# motherboard.net
KiCad netlist of a schematic drawn in Altium Designer
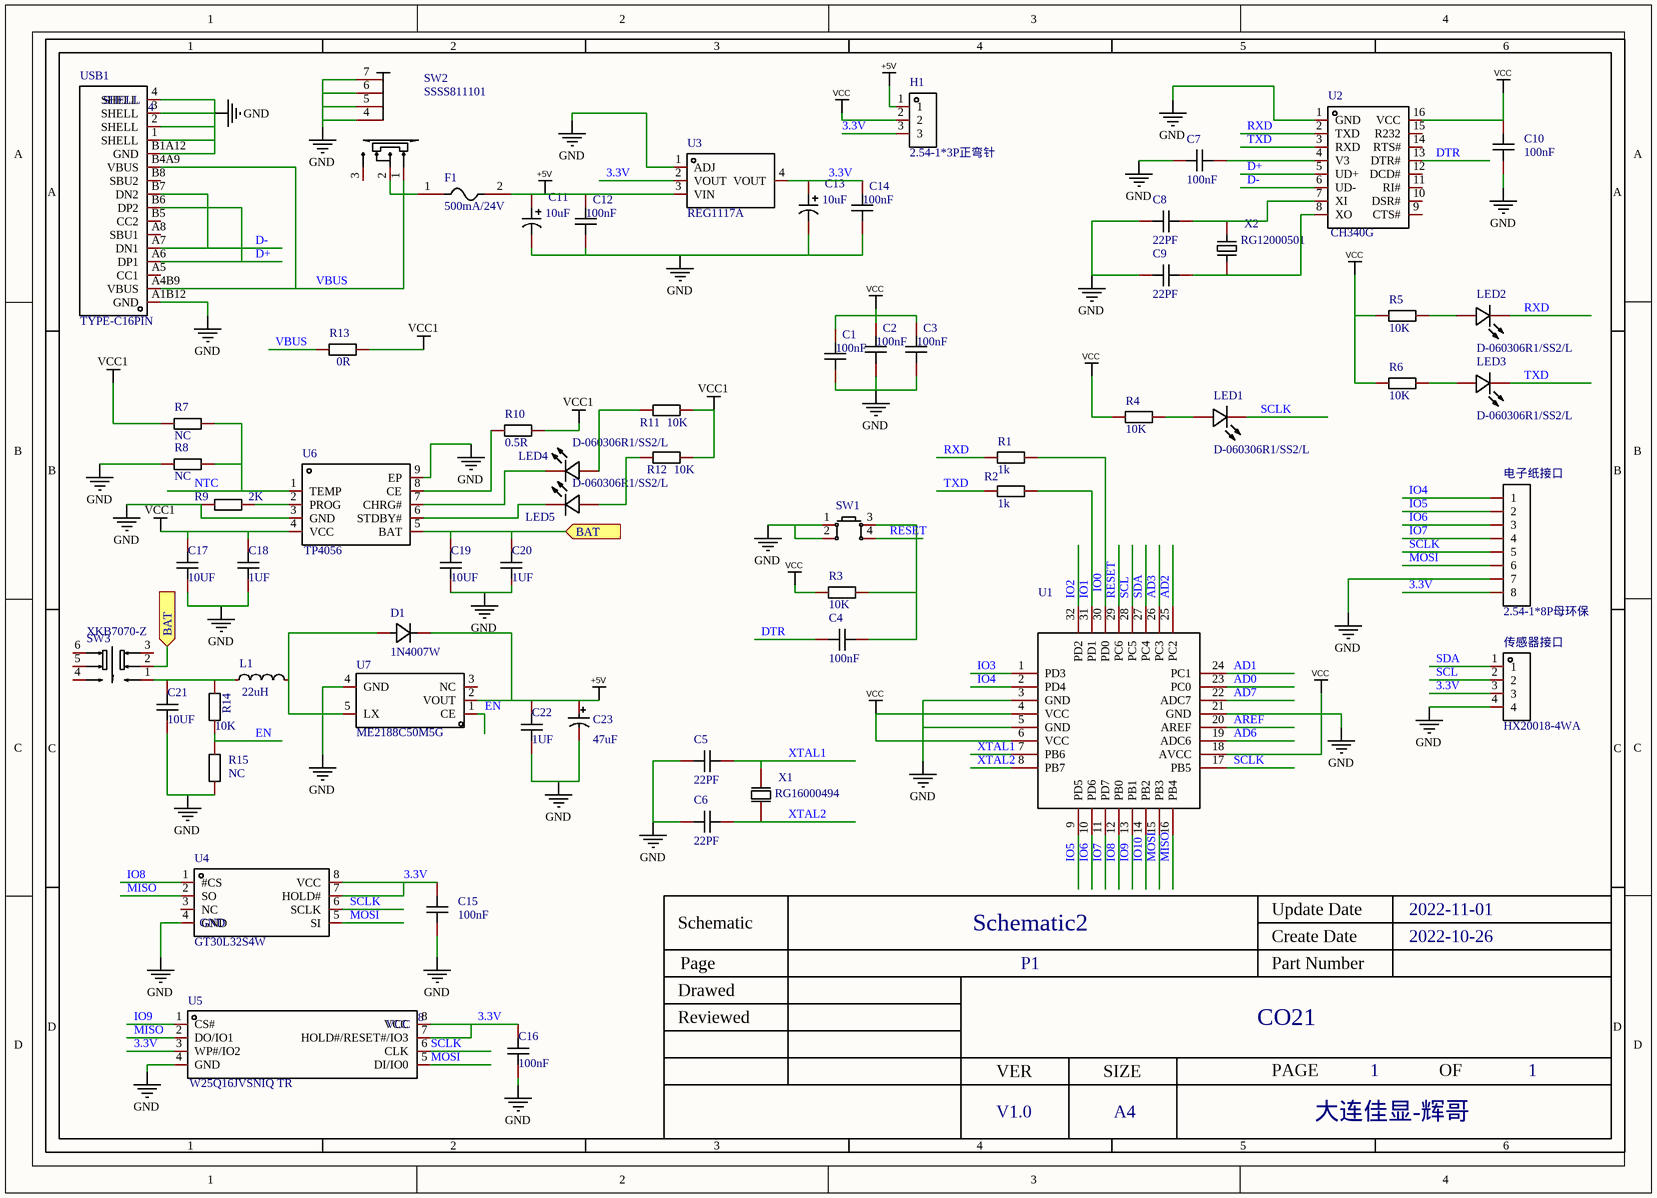
[diagram p0: motherboard.schdoc]

(export (version "E")
  (design (tool "Eeschema 10.0.6"))
  (components
    (comp (ref "C1")
      (value "100nF")
      (fields (field (name "NAME") "100nF"))
      (libsource (lib "altium-import") (part "root_1_CAP_0603_"))
    )
    (comp (ref "C2")
      (value "100nF")
      (fields (field (name "NAME") "100nF"))
      (libsource (lib "altium-import") (part "root_1_CAP_0603_"))
    )
    (comp (ref "C3")
      (value "100nF")
      (fields (field (name "NAME") "100nF"))
      (libsource (lib "altium-import") (part "root_1_CAP_0603_"))
    )
    (comp (ref "C4")
      (value "100nF")
      (fields (field (name "NAME") "100nF"))
      (libsource (lib "altium-import") (part "root_2_CAP_0603_"))
    )
    (comp (ref "C5")
      (value "22PF")
      (fields (field (name "NAME") "22PF"))
      (libsource (lib "altium-import") (part "root_2_CAP_0603_"))
    )
    (comp (ref "C6")
      (value "22PF")
      (fields (field (name "NAME") "22PF"))
      (libsource (lib "altium-import") (part "root_2_CAP_0603_"))
    )
    (comp (ref "C7")
      (value "100nF")
      (fields (field (name "NAME") "100nF"))
      (libsource (lib "altium-import") (part "root_0_CAP_0603_"))
    )
    (comp (ref "C8")
      (value "22PF")
      (fields (field (name "NAME") "22PF"))
      (libsource (lib "altium-import") (part "root_2_CAP_0603_"))
    )
    (comp (ref "C9")
      (value "22PF")
      (fields (field (name "NAME") "22PF"))
      (libsource (lib "altium-import") (part "root_2_CAP_0603_"))
    )
    (comp (ref "C10")
      (value "100nF")
      (fields (field (name "NAME") "100nF"))
      (libsource (lib "altium-import") (part "root_1_CAP_0603_"))
    )
    (comp (ref "C11")
      (value "10uF")
      (description "容值:10uF;精度:±10%;额定电压:20V;工作温度:-55~+125;")
      (fields
        (field (name "NAME") "10uF")
        (field (name "MANUFACTURER") "CEC(振华新云)")
        (field (name "MANUFACTURER PART") "CA45A-B-20V-10UF-K")
      )
      (libsource (lib "altium-import") (part "root_3_CA45A-B-20V-10UF-K_"))
    )
    (comp (ref "C12")
      (value "100nF")
      (fields (field (name "NAME") "100nF"))
      (libsource (lib "altium-import") (part "root_1_CAP_0603_"))
    )
    (comp (ref "C13")
      (value "10uF")
      (description "容值:10uF;精度:±10%;额定电压:20V;工作温度:-55~+125;")
      (fields
        (field (name "NAME") "10uF")
        (field (name "MANUFACTURER") "CEC(振华新云)")
        (field (name "MANUFACTURER PART") "CA45A-B-20V-10UF-K")
      )
      (libsource (lib "altium-import") (part "root_3_CA45A-B-20V-10UF-K_"))
    )
    (comp (ref "C14")
      (value "100nF")
      (fields (field (name "NAME") "100nF"))
      (libsource (lib "altium-import") (part "root_1_CAP_0603_"))
    )
    (comp (ref "C15")
      (value "100nF")
      (fields (field (name "NAME") "100nF"))
      (libsource (lib "altium-import") (part "root_3_CAP_0603_"))
    )
    (comp (ref "C16")
      (value "100nF")
      (fields (field (name "NAME") "100nF"))
      (libsource (lib "altium-import") (part "root_3_CAP_0603_"))
    )
    (comp (ref "C17")
      (value "10UF")
      (fields (field (name "NAME") "10UF"))
      (libsource (lib "altium-import") (part "root_3_CAP_0603_"))
    )
    (comp (ref "C18")
      (value "1UF")
      (fields (field (name "NAME") "1UF"))
      (libsource (lib "altium-import") (part "root_3_CAP_0603_"))
    )
    (comp (ref "C19")
      (value "10UF")
      (fields (field (name "NAME") "10UF"))
      (libsource (lib "altium-import") (part "root_3_CAP_0603_"))
    )
    (comp (ref "C20")
      (value "1UF")
      (fields (field (name "NAME") "1UF"))
      (libsource (lib "altium-import") (part "root_3_CAP_0603_"))
    )
    (comp (ref "C21")
      (value "10UF")
      (fields (field (name "NAME") "10UF"))
      (libsource (lib "altium-import") (part "root_3_CAP_0603_"))
    )
    (comp (ref "C22")
      (value "1UF")
      (fields (field (name "NAME") "1UF"))
      (libsource (lib "altium-import") (part "root_3_CAP_0603_"))
    )
    (comp (ref "C23")
      (value "47uF")
      (description "容值:47uF;精度:±20%;额定电压:10V;电容体直径:4mm;电容体长度:5mm;脚间距:1.5mm;工作寿命:1000hrs@105;")
      (fields
        (field (name "NAME") "47uF")
        (field (name "MANUFACTURER") "CX(承兴)")
        (field (name "MANUFACTURER PART") "KF476M010C05RR0VH2FP0")
      )
      (libsource (lib "altium-import") (part "root_3_KF476M010C05RR0VH2FP0_"))
    )
    (comp (ref "D1")
      (value "1N4007W")
      (description "二极管配置:独立式;直流反向耐压(Vr):1kV;平均整流电流(Io):1A;正向压降(Vf):1.1V@1A;反向电流(Ir):5A@1kV;")
      (fields (field (name "NAME") "1N4007W") (field (name "MANUFACTURER") "ST(先科)"))
      (libsource (lib "altium-import") (part "root_2_1N4007W_C725740_"))
    )
    (comp (ref "F1")
      (value "500mA/24V")
      (fields (field (name "NAME") "500mA/24V") (field (name "MANUFACTURER") "DOWO(东沃)"))
      (libsource (lib "altium-import") (part "root_0_500mA/24V_"))
    )
    (comp (ref "H1")
      (value "2.54-1*3P正弯针")
      (fields (field (name "NAME") "2.54-1*3P正弯针") (field (name "MANUFACTURER") "BOOMELE(博穆精密)"))
      (libsource (lib "altium-import") (part "root_0_2.54-1*3P正弯针_"))
    )
    (comp (ref "L1")
      (value "22uH")
      (description "电感值:22uH;精度:±20%;额定电流:1.4A;直流电阻(DCR):174mΩ;")
      (fields
        (field (name "NAME") "22uH")
        (field (name "MANUFACTURER") "SXN(顺翔诺)")
        (field (name "MANUFACTURER PART") "SMNR5040-220MT")
      )
      (libsource (lib "altium-import") (part "root_0_SMNR5040-220MT_"))
    )
    (comp (ref "LED1")
      (value "D-060306R1/SS2/L")
      (description "发光颜色:红灯;")
      (fields (field (name "NAME") "D-060306R1/SS2/L") (field (name "MANUFACTURER") "方舟 ARKLED"))
      (libsource (lib "altium-import") (part "root_2_D-060306R1/SS2/L_"))
    )
    (comp (ref "LED2")
      (value "D-060306R1/SS2/L")
      (description "发光颜色:红灯;")
      (fields (field (name "NAME") "D-060306R1/SS2/L") (field (name "MANUFACTURER") "方舟 ARKLED"))
      (libsource (lib "altium-import") (part "root_2_D-060306R1/SS2/L_"))
    )
    (comp (ref "LED3")
      (value "D-060306R1/SS2/L")
      (description "发光颜色:红灯;")
      (fields (field (name "NAME") "D-060306R1/SS2/L") (field (name "MANUFACTURER") "方舟 ARKLED"))
      (libsource (lib "altium-import") (part "root_2_D-060306R1/SS2/L_"))
    )
    (comp (ref "LED4")
      (value "D-060306R1/SS2/L")
      (description "发光颜色:红灯;")
      (fields (field (name "NAME") "D-060306R1/SS2/L") (field (name "MANUFACTURER") "方舟 ARKLED"))
      (libsource (lib "altium-import") (part "root_0_D-060306R1/SS2/L_"))
    )
    (comp (ref "LED5")
      (value "D-060306R1/SS2/L")
      (description "发光颜色:红灯;")
      (fields (field (name "NAME") "D-060306R1/SS2/L") (field (name "MANUFACTURER") "方舟 ARKLED"))
      (libsource (lib "altium-import") (part "root_0_D-060306R1/SS2/L_"))
    )
    (comp (ref "R1")
      (value "1k")
      (fields (field (name "NAME") "1k"))
      (libsource (lib "altium-import") (part "root_0_Res_0603_"))
    )
    (comp (ref "R2")
      (value "1k")
      (fields (field (name "NAME") "1k"))
      (libsource (lib "altium-import") (part "root_0_Res_0603_"))
    )
    (comp (ref "R3")
      (value "10K")
      (fields (field (name "NAME") "10K"))
      (libsource (lib "altium-import") (part "root_0_Res_0603_"))
    )
    (comp (ref "R4")
      (value "10K")
      (fields (field (name "NAME") "10K"))
      (libsource (lib "altium-import") (part "root_0_Res_0603_"))
    )
    (comp (ref "R5")
      (value "10K")
      (fields (field (name "NAME") "10K"))
      (libsource (lib "altium-import") (part "root_0_Res_0603_"))
    )
    (comp (ref "R6")
      (value "10K")
      (fields (field (name "NAME") "10K"))
      (libsource (lib "altium-import") (part "root_0_Res_0603_"))
    )
    (comp (ref "R7")
      (value "NC")
      (fields (field (name "NAME") "NC"))
      (libsource (lib "altium-import") (part "root_0_Res_0603_"))
    )
    (comp (ref "R8")
      (value "NC")
      (fields (field (name "NAME") "NC"))
      (libsource (lib "altium-import") (part "root_0_Res_0603_"))
    )
    (comp (ref "R9")
      (value "2K")
      (fields (field (name "NAME") "2K"))
      (libsource (lib "altium-import") (part "root_0_Res_0603_"))
    )
    (comp (ref "R10")
      (value "0.5R")
      (fields (field (name "NAME") "0.5R"))
      (libsource (lib "altium-import") (part "root_0_Res_0603_"))
    )
    (comp (ref "R11")
      (value "10K")
      (fields (field (name "NAME") "10K"))
      (libsource (lib "altium-import") (part "root_0_Res_0603_"))
    )
    (comp (ref "R12")
      (value "10K")
      (fields (field (name "NAME") "10K"))
      (libsource (lib "altium-import") (part "root_0_Res_0603_"))
    )
    (comp (ref "R13")
      (value "0R")
      (fields (field (name "NAME") "0R"))
      (libsource (lib "altium-import") (part "root_0_Res_0603_"))
    )
    (comp (ref "R14")
      (value "10K")
      (fields (field (name "NAME") "10K"))
      (libsource (lib "altium-import") (part "root_1_Res_0603_"))
    )
    (comp (ref "R15")
      (value "NC")
      (fields (field (name "NAME") "NC"))
      (libsource (lib "altium-import") (part "root_1_Res_0603_"))
    )
    (comp (ref "SW1")
      (value "Key_SMD_6x6x6.5")
      (description "触点电流:50mA;额定电压(DC):12V;电路结构:单刀单掷;安装方式:立贴;按钮形状:圆形按钮;带灯:-;开关长度:6mm;开关宽度:6mm;开关高度:6.5mm;")
      (libsource (lib "altium-import") (part "root_0_Key_SMD_6x6x6.5_"))
    )
    (comp (ref "SW2")
      (value "SSSS811101")
      (fields (field (name "NAME") "SSSS811101") (field (name "MANUFACTURER") "ALPSALPINE(阿尔卑斯阿尔派)"))
      (libsource (lib "altium-import") (part "root_2_SSSS811101_"))
    )
    (comp (ref "SW3")
      (value "XKB7070-Z")
      (fields (field (name "NAME") "XKB7070-Z") (field (name "MANUFACTURER") "XKB Connectivity(中国星坤)"))
      (libsource (lib "altium-import") (part "root_2_XKB7070-Z_"))
    )
    (comp (ref "U1") (value "EGA328p") (libsource (lib "altium-import") (part "root_0_EGA328p_")))
    (comp (ref "U2")
      (value "CH340G")
      (description "类型:Transceiver;协议类别:USB 2.0;驱动器/接收器数:-;数据速率:2Mbps;")
      (fields (field (name "NAME") "CH340G") (field (name "MANUFACTURER") "WCH(南京沁恒)"))
      (libsource (lib "altium-import") (part "root_0_CH340G_"))
    )
    (comp (ref "U3")
      (value "REG1117A")
      (fields (field (name "NAME") "REG1117A") (field (name "MANUFACTURER") "TI(德州仪器)"))
      (libsource (lib "altium-import") (part "root_0_REG1117A_"))
    )
    (comp (ref "U4")
      (value "GT30L32S4W")
      (description "字符集:-;点阵大小:-;时钟频率:-;工作温度:-;")
      (fields
        (field (name "NAME") "GT30L32S4W")
        (field (name "MANUFACTURER") "GENITOP(高通)")
        (field (name "NAME_1") "GND")
      )
      (libsource (lib "altium-import") (part "root_0_GT30L32S4W_"))
    )
    (comp (ref "U5")
      (value "W25Q16JVSNIQ TR")
      (fields
        (field (name "NAME") "W25Q16JVSNIQ TR")
        (field (name "MANUFACTURER") "WINBOND(华邦)")
        (field (name "NAME_1") "VCC")
        (field (name "NUMBER") "8")
      )
      (libsource (lib "altium-import") (part "root_0_W25Q16JVSNIQ TR_"))
    )
    (comp (ref "U6")
      (value "TP4056")
      (fields (field (name "NAME") "TP4056") (field (name "MANUFACTURER") "UMW(友台半导体)"))
      (libsource (lib "altium-import") (part "root_0_TP4056_C725790_"))
    )
    (comp (ref "U7")
      (value "ME2188C50M5G")
      (description "功能类型:升压型;同步整流:是;输出通道数:1;拓扑结构:升压式;输入电压:0.9V~5V;输出电压:5V;输出电流(最大值):300mA;开关频率:320kHz;")
      (fields (field (name "NAME") "ME2188C50M5G") (field (name "MANUFACTURER") "MICRONE(南京微盟)"))
      (libsource (lib "altium-import") (part "root_2_ME2188C50M5G_"))
    )
    (comp (ref "USB1")
      (value "TYPE-C16PIN")
      (description "连接器类型:Type-C;标准:-;公母:母座;触点数量:16;端口数量:1;安装方式:卧贴;额定电流 - 电源:3A;工作温度范围:-40~+85;")
      (fields
        (field (name "NAME") "TYPE-C16PIN")
        (field (name "MANUFACTURER") "SHOU HAN(首韩)")
        (field (name "NUMBER") "4")
        (field (name "NAME_1") "SHELL")
      )
      (libsource (lib "altium-import") (part "root_2_TYPE-C16PIN_"))
    )
    (comp (ref "X1")
      (value "RG16000494")
      (description "GLASS5032-2P")
      (fields (field (name "NAME") "RG16000494") (field (name "MANUFACTURER") "TROQ(创捷)"))
      (libsource (lib "altium-import") (part "root_1_RG16000494_"))
    )
    (comp (ref "X2")
      (value "RG12000501")
      (description "GLASS5032-2P")
      (fields (field (name "NAME") "RG12000501") (field (name "MANUFACTURER") "TROQ(创捷)"))
      (libsource (lib "altium-import") (part "root_1_RG12000501_"))
    )
    (comp (ref "传感器接口")
      (value "HX20018-4WA")
      (description "参考系列:-;间距:2mm;插针结构:1x4P;排数:1;每排PIN数:4;行距:-;公母:公型插针;安装方式:弯插;额定电流:3A;工作温度范围:-25~+85;")
      (fields (field (name "NAME") "HX20018-4WA") (field (name "MANUFACTURER") "HX(红星)"))
      (libsource (lib "altium-import") (part "root_0_HX20018-4WA_"))
    )
    (comp (ref "电子纸接口")
      (value "2.54-1*8P母环保")
      (description "间距:2.54mm;总孔位数:8;排数:1;插孔结构:1x8P;行距:-;安装类型:直插;塑高:-;触头材质:-;触头镀层:-;")
      (fields (field (name "NAME") "2.54-1*8P母环保") (field (name "MANUFACTURER") "BOOMELE(博穆精密)"))
      (libsource (lib "altium-import") (part "root_0_2.54-1*8P母环保_"))
    )
  )
  (nets
    (net (code "1") (name "+5V") (class "Default")
      (node (ref "C11") (pin "1") (pinfunction "1_1") (pintype "passive"))
      (node (ref "C12") (pin "2") (pinfunction "2_2") (pintype "passive"))
      (node (ref "C22") (pin "1") (pinfunction "1_1") (pintype "passive"))
      (node (ref "C23") (pin "1") (pinfunction "1_1") (pintype "passive"))
      (node (ref "D1") (pin "1") (pinfunction "K_1") (pintype "passive"))
      (node (ref "F1") (pin "2") (pinfunction "2_2") (pintype "passive"))
      (node (ref "H1") (pin "1") (pinfunction "1_1") (pintype "passive"))
      (node (ref "U3") (pin "3") (pinfunction "VIN_3") (pintype "passive"))
      (node (ref "U7") (pin "2") (pinfunction "VOUT_2") (pintype "passive"))
    )
    (net (code "2") (name "/3.3V") (class "Default")
      (node (ref "C13") (pin "1") (pinfunction "1_1") (pintype "passive"))
      (node (ref "C14") (pin "2") (pinfunction "2_2") (pintype "passive"))
      (node (ref "C15") (pin "1") (pinfunction "1_1") (pintype "passive"))
      (node (ref "C16") (pin "1") (pinfunction "1_1") (pintype "passive"))
      (node (ref "H1") (pin "3") (pinfunction "3_3") (pintype "passive"))
      (node (ref "U3") (pin "2") (pinfunction "VOUT_2") (pintype "passive"))
      (node (ref "U3") (pin "4") (pinfunction "VOUT_4") (pintype "passive"))
      (node (ref "U4") (pin "7") (pinfunction "HOLD#_7") (pintype "passive"))
      (node (ref "U4") (pin "8") (pinfunction "VCC_8") (pintype "passive"))
      (node (ref "U5") (pin "3") (pinfunction "WP#/IO2_3") (pintype "passive"))
      (node (ref "U5") (pin "7") (pinfunction "HOLD#/RESET#/IO3_7") (pintype "passive"))
      (node (ref "U5") (pin "8") (pinfunction "VCC_8") (pintype "passive"))
      (node (ref "传感器接口") (pin "3") (pinfunction "3_3") (pintype "passive"))
      (node (ref "电子纸接口") (pin "8") (pinfunction "8_8") (pintype "passive"))
    )
    (net (code "3") (name "/AD0") (class "Default")
      (node (ref "U1") (pin "23") (pinfunction "PC0_23") (pintype "passive"))
    )
    (net (code "4") (name "/AD1") (class "Default")
      (node (ref "U1") (pin "24") (pinfunction "PC1_24") (pintype "passive"))
    )
    (net (code "5") (name "/AD2") (class "Default")
      (node (ref "U1") (pin "25") (pinfunction "PC2_25") (pintype "passive"))
    )
    (net (code "6") (name "/AD3") (class "Default")
      (node (ref "U1") (pin "26") (pinfunction "PC3_26") (pintype "passive"))
    )
    (net (code "7") (name "/AD6") (class "Default")
      (node (ref "U1") (pin "19") (pinfunction "ADC6_19") (pintype "passive"))
    )
    (net (code "8") (name "/AD7") (class "Default")
      (node (ref "U1") (pin "22") (pinfunction "ADC7_22") (pintype "passive"))
    )
    (net (code "9") (name "/AREF") (class "Default")
      (node (ref "U1") (pin "20") (pinfunction "AREF_20") (pintype "passive"))
    )
    (net (code "10") (name "/BAT") (class "Default")
      (node (ref "C19") (pin "1") (pinfunction "1_1") (pintype "passive"))
      (node (ref "C20") (pin "1") (pinfunction "1_1") (pintype "passive"))
      (node (ref "SW3") (pin "2") (pinfunction "2_2") (pintype "passive"))
      (node (ref "U6") (pin "5") (pinfunction "BAT_5") (pintype "passive"))
    )
    (net (code "11") (name "/D+") (class "Default")
      (node (ref "U2") (pin "5") (pinfunction "UD+_5") (pintype "passive"))
      (node (ref "USB1") (pin "A6") (pinfunction "DP1_A6") (pintype "passive"))
      (node (ref "USB1") (pin "B6") (pinfunction "DP2_B6") (pintype "passive"))
    )
    (net (code "12") (name "/D-") (class "Default")
      (node (ref "U2") (pin "6") (pinfunction "UD-_6") (pintype "passive"))
      (node (ref "USB1") (pin "A7") (pinfunction "DN1_A7") (pintype "passive"))
      (node (ref "USB1") (pin "B7") (pinfunction "DN2_B7") (pintype "passive"))
    )
    (net (code "13") (name "/DTR") (class "Default")
      (node (ref "C4") (pin "2") (pinfunction "2_2") (pintype "passive"))
      (node (ref "U2") (pin "13") (pinfunction "DTR#_13") (pintype "passive"))
    )
    (net (code "14") (name "/EN") (class "Default")
      (node (ref "R14") (pin "1") (pinfunction "1_1") (pintype "passive"))
      (node (ref "R15") (pin "2") (pinfunction "2_2") (pintype "passive"))
      (node (ref "U7") (pin "1") (pinfunction "CE_1") (pintype "passive"))
    )
    (net (code "15") (name "/IO0") (class "Default")
      (node (ref "R1") (pin "2") (pinfunction "2_2") (pintype "passive"))
      (node (ref "U1") (pin "30") (pinfunction "PD0_30") (pintype "passive"))
    )
    (net (code "16") (name "/IO1") (class "Default")
      (node (ref "R2") (pin "2") (pinfunction "2_2") (pintype "passive"))
      (node (ref "U1") (pin "31") (pinfunction "PD1_31") (pintype "passive"))
    )
    (net (code "17") (name "/IO2") (class "Default")
      (node (ref "U1") (pin "32") (pinfunction "PD2_32") (pintype "passive"))
    )
    (net (code "18") (name "/IO3") (class "Default")
      (node (ref "U1") (pin "1") (pinfunction "PD3_1") (pintype "passive"))
    )
    (net (code "19") (name "/IO4") (class "Default")
      (node (ref "U1") (pin "2") (pinfunction "PD4_2") (pintype "passive"))
      (node (ref "电子纸接口") (pin "1") (pinfunction "1_1") (pintype "passive"))
    )
    (net (code "20") (name "/IO5") (class "Default")
      (node (ref "U1") (pin "9") (pinfunction "PD5_9") (pintype "passive"))
      (node (ref "电子纸接口") (pin "2") (pinfunction "2_2") (pintype "passive"))
    )
    (net (code "21") (name "/IO6") (class "Default")
      (node (ref "U1") (pin "10") (pinfunction "PD6_10") (pintype "passive"))
      (node (ref "电子纸接口") (pin "3") (pinfunction "3_3") (pintype "passive"))
    )
    (net (code "22") (name "/IO7") (class "Default")
      (node (ref "U1") (pin "11") (pinfunction "PD7_11") (pintype "passive"))
      (node (ref "电子纸接口") (pin "4") (pinfunction "4_4") (pintype "passive"))
    )
    (net (code "23") (name "/IO8") (class "Default")
      (node (ref "U1") (pin "12") (pinfunction "PB0_12") (pintype "passive"))
      (node (ref "U4") (pin "1") (pinfunction "#CS_1") (pintype "passive"))
    )
    (net (code "24") (name "/IO9") (class "Default")
      (node (ref "U1") (pin "13") (pinfunction "PB1_13") (pintype "passive"))
      (node (ref "U5") (pin "1") (pinfunction "CS#_1") (pintype "passive"))
    )
    (net (code "25") (name "/IO10") (class "Default")
      (node (ref "U1") (pin "14") (pinfunction "PB2_14") (pintype "passive"))
    )
    (net (code "26") (name "/MISO") (class "Default")
      (node (ref "U1") (pin "16") (pinfunction "PB4_16") (pintype "passive"))
      (node (ref "U4") (pin "2") (pinfunction "SO_2") (pintype "passive"))
      (node (ref "U5") (pin "2") (pinfunction "DO/IO1_2") (pintype "passive"))
    )
    (net (code "27") (name "/MOSI") (class "Default")
      (node (ref "U1") (pin "15") (pinfunction "PB3_15") (pintype "passive"))
      (node (ref "U4") (pin "5") (pinfunction "SI_5") (pintype "passive"))
      (node (ref "U5") (pin "5") (pinfunction "DI/IO0_5") (pintype "passive"))
      (node (ref "电子纸接口") (pin "6") (pinfunction "6_6") (pintype "passive"))
    )
    (net (code "28") (name "/NTC") (class "Default")
      (node (ref "R7") (pin "2") (pinfunction "2_2") (pintype "passive"))
      (node (ref "R8") (pin "2") (pinfunction "2_2") (pintype "passive"))
      (node (ref "U6") (pin "1") (pinfunction "TEMP_1") (pintype "passive"))
    )
    (net (code "29") (name "/RESET") (class "Default")
      (node (ref "C4") (pin "1") (pinfunction "1_1") (pintype "passive"))
      (node (ref "R3") (pin "2") (pinfunction "2_2") (pintype "passive"))
      (node (ref "SW1") (pin "3") (pinfunction "3_3") (pintype "passive"))
      (node (ref "SW1") (pin "4") (pinfunction "4_4") (pintype "passive"))
      (node (ref "U1") (pin "29") (pinfunction "PC6_29") (pintype "passive"))
    )
    (net (code "30") (name "/RXD") (class "Default")
      (node (ref "LED2") (pin "1") (pinfunction "-_1") (pintype "passive"))
      (node (ref "R1") (pin "1") (pinfunction "1_1") (pintype "passive"))
      (node (ref "U2") (pin "2") (pinfunction "TXD_2") (pintype "passive"))
    )
    (net (code "31") (name "/SCL") (class "Default")
      (node (ref "U1") (pin "28") (pinfunction "PC5_28") (pintype "passive"))
      (node (ref "传感器接口") (pin "2") (pinfunction "2_2") (pintype "passive"))
    )
    (net (code "32") (name "/SCLK") (class "Default")
      (node (ref "LED1") (pin "1") (pinfunction "-_1") (pintype "passive"))
      (node (ref "U1") (pin "17") (pinfunction "PB5_17") (pintype "passive"))
      (node (ref "U4") (pin "6") (pinfunction "SCLK_6") (pintype "passive"))
      (node (ref "U5") (pin "6") (pinfunction "CLK_6") (pintype "passive"))
      (node (ref "电子纸接口") (pin "5") (pinfunction "5_5") (pintype "passive"))
    )
    (net (code "33") (name "/SDA") (class "Default")
      (node (ref "U1") (pin "27") (pinfunction "PC4_27") (pintype "passive"))
      (node (ref "传感器接口") (pin "1") (pinfunction "1_1") (pintype "passive"))
    )
    (net (code "34") (name "/TXD") (class "Default")
      (node (ref "LED3") (pin "1") (pinfunction "-_1") (pintype "passive"))
      (node (ref "R2") (pin "1") (pinfunction "1_1") (pintype "passive"))
      (node (ref "U2") (pin "3") (pinfunction "RXD_3") (pintype "passive"))
    )
    (net (code "35") (name "/VBUS") (class "Default")
      (node (ref "R13") (pin "1") (pinfunction "1_1") (pintype "passive"))
      (node (ref "SW2") (pin "1") (pinfunction "1_1") (pintype "passive"))
      (node (ref "USB1") (pin "A4B9") (pinfunction "VBUS_A4B9") (pintype "passive"))
      (node (ref "USB1") (pin "B4A9") (pinfunction "VBUS_B4A9") (pintype "passive"))
    )
    (net (code "36") (name "/XTAL1") (class "Default")
      (node (ref "C5") (pin "1") (pinfunction "1_1") (pintype "passive"))
      (node (ref "U1") (pin "7") (pinfunction "PB6_7") (pintype "passive"))
      (node (ref "X1") (pin "2") (pinfunction "OSC2_2") (pintype "passive"))
    )
    (net (code "37") (name "/XTAL2") (class "Default")
      (node (ref "C6") (pin "1") (pinfunction "1_1") (pintype "passive"))
      (node (ref "U1") (pin "8") (pinfunction "PB7_8") (pintype "passive"))
      (node (ref "X1") (pin "1") (pinfunction "OSC1_1") (pintype "passive"))
    )
    (net (code "38") (name "GND") (class "Default")
      (node (ref "C1") (pin "1") (pinfunction "1_1") (pintype "passive"))
      (node (ref "C10") (pin "1") (pinfunction "1_1") (pintype "passive"))
      (node (ref "C11") (pin "2") (pinfunction "2_2") (pintype "passive"))
      (node (ref "C12") (pin "1") (pinfunction "1_1") (pintype "passive"))
      (node (ref "C13") (pin "2") (pinfunction "2_2") (pintype "passive"))
      (node (ref "C14") (pin "1") (pinfunction "1_1") (pintype "passive"))
      (node (ref "C15") (pin "2") (pinfunction "2_2") (pintype "passive"))
      (node (ref "C16") (pin "2") (pinfunction "2_2") (pintype "passive"))
      (node (ref "C17") (pin "2") (pinfunction "2_2") (pintype "passive"))
      (node (ref "C18") (pin "2") (pinfunction "2_2") (pintype "passive"))
      (node (ref "C19") (pin "2") (pinfunction "2_2") (pintype "passive"))
      (node (ref "C2") (pin "1") (pinfunction "1_1") (pintype "passive"))
      (node (ref "C20") (pin "2") (pinfunction "2_2") (pintype "passive"))
      (node (ref "C21") (pin "2") (pinfunction "2_2") (pintype "passive"))
      (node (ref "C22") (pin "2") (pinfunction "2_2") (pintype "passive"))
      (node (ref "C23") (pin "2") (pinfunction "2_2") (pintype "passive"))
      (node (ref "C3") (pin "1") (pinfunction "1_1") (pintype "passive"))
      (node (ref "C5") (pin "2") (pinfunction "2_2") (pintype "passive"))
      (node (ref "C6") (pin "2") (pinfunction "2_2") (pintype "passive"))
      (node (ref "C7") (pin "1") (pinfunction "1_1") (pintype "passive"))
      (node (ref "C8") (pin "2") (pinfunction "2_2") (pintype "passive"))
      (node (ref "C9") (pin "2") (pinfunction "2_2") (pintype "passive"))
      (node (ref "R15") (pin "1") (pinfunction "1_1") (pintype "passive"))
      (node (ref "R8") (pin "1") (pinfunction "1_1") (pintype "passive"))
      (node (ref "R9") (pin "1") (pinfunction "1_1") (pintype "passive"))
      (node (ref "SW1") (pin "1") (pinfunction "1_1") (pintype "passive"))
      (node (ref "SW1") (pin "2") (pinfunction "2_2") (pintype "passive"))
      (node (ref "SW2") (pin "4") (pinfunction "4_4") (pintype "passive"))
      (node (ref "SW2") (pin "5") (pinfunction "5_5") (pintype "passive"))
      (node (ref "SW2") (pin "6") (pinfunction "6_6") (pintype "passive"))
      (node (ref "SW2") (pin "7") (pinfunction "7_7") (pintype "passive"))
      (node (ref "U1") (pin "21") (pinfunction "GND_21") (pintype "passive"))
      (node (ref "U1") (pin "3") (pinfunction "GND_3") (pintype "passive"))
      (node (ref "U1") (pin "5") (pinfunction "GND_5") (pintype "passive"))
      (node (ref "U2") (pin "1") (pinfunction "GND_1") (pintype "passive"))
      (node (ref "U3") (pin "1") (pinfunction "ADJ_1") (pintype "passive"))
      (node (ref "U4") (pin "4") (pinfunction "GND_4") (pintype "passive"))
      (node (ref "U5") (pin "4") (pinfunction "GND_4") (pintype "passive"))
      (node (ref "U6") (pin "3") (pinfunction "GND_3") (pintype "passive"))
      (node (ref "U6") (pin "9") (pinfunction "EP_9") (pintype "passive"))
      (node (ref "U7") (pin "4") (pinfunction "GND_4") (pintype "passive"))
      (node (ref "USB1") (pin "1") (pinfunction "SHELL_1") (pintype "passive"))
      (node (ref "USB1") (pin "2") (pinfunction "SHELL_2") (pintype "passive"))
      (node (ref "USB1") (pin "3") (pinfunction "SHELL_3") (pintype "passive"))
      (node (ref "USB1") (pin "4") (pinfunction "SHELL_4") (pintype "passive"))
      (node (ref "USB1") (pin "A1B12") (pinfunction "GND_A1B12") (pintype "passive"))
      (node (ref "USB1") (pin "B1A12") (pinfunction "GND_B1A12") (pintype "passive"))
      (node (ref "传感器接口") (pin "4") (pinfunction "4_4") (pintype "passive"))
      (node (ref "电子纸接口") (pin "7") (pinfunction "7_7") (pintype "passive"))
    )
    (net (code "39") (name "Net-(C21-Pad1)") (class "Default")
      (node (ref "C21") (pin "1") (pinfunction "1_1") (pintype "passive"))
      (node (ref "L1") (pin "1") (pinfunction "1_1") (pintype "passive"))
      (node (ref "R14") (pin "2") (pinfunction "2_2") (pintype "passive"))
      (node (ref "SW3") (pin "1") (pinfunction "1_1") (pintype "passive"))
    )
    (net (code "40") (name "Net-(D1-A)") (class "Default")
      (node (ref "D1") (pin "2") (pinfunction "A_2") (pintype "passive"))
      (node (ref "L1") (pin "2") (pinfunction "2_2") (pintype "passive"))
      (node (ref "U7") (pin "5") (pinfunction "LX_5") (pintype "passive"))
    )
    (net (code "41") (name "Net-(F1-Pad1)") (class "Default")
      (node (ref "F1") (pin "1") (pinfunction "1_1") (pintype "passive"))
      (node (ref "SW2") (pin "2") (pinfunction "2_2") (pintype "passive"))
    )
    (net (code "42") (name "Net-(LED1-+)") (class "Default")
      (node (ref "LED1") (pin "2") (pinfunction "+_2") (pintype "passive"))
      (node (ref "R4") (pin "2") (pinfunction "2_2") (pintype "passive"))
    )
    (net (code "43") (name "Net-(LED2-+)") (class "Default")
      (node (ref "LED2") (pin "2") (pinfunction "+_2") (pintype "passive"))
      (node (ref "R5") (pin "2") (pinfunction "2_2") (pintype "passive"))
    )
    (net (code "44") (name "Net-(LED3-+)") (class "Default")
      (node (ref "LED3") (pin "2") (pinfunction "+_2") (pintype "passive"))
      (node (ref "R6") (pin "2") (pinfunction "2_2") (pintype "passive"))
    )
    (net (code "45") (name "Net-(LED4-+)") (class "Default")
      (node (ref "LED4") (pin "2") (pinfunction "+_2") (pintype "passive"))
      (node (ref "R11") (pin "1") (pinfunction "1_1") (pintype "passive"))
    )
    (net (code "46") (name "Net-(LED4--)") (class "Default")
      (node (ref "LED4") (pin "1") (pinfunction "-_1") (pintype "passive"))
      (node (ref "U6") (pin "7") (pinfunction "CHRG#_7") (pintype "passive"))
    )
    (net (code "47") (name "Net-(LED5-+)") (class "Default")
      (node (ref "LED5") (pin "2") (pinfunction "+_2") (pintype "passive"))
      (node (ref "R12") (pin "1") (pinfunction "1_1") (pintype "passive"))
    )
    (net (code "48") (name "Net-(LED5--)") (class "Default")
      (node (ref "LED5") (pin "1") (pinfunction "-_1") (pintype "passive"))
      (node (ref "U6") (pin "6") (pinfunction "STDBY#_6") (pintype "passive"))
    )
    (net (code "49") (name "Net-(U2-V3)") (class "Default")
      (node (ref "C7") (pin "2") (pinfunction "2_2") (pintype "passive"))
      (node (ref "U2") (pin "4") (pinfunction "V3_4") (pintype "passive"))
    )
    (net (code "50") (name "Net-(U2-XI)") (class "Default")
      (node (ref "C8") (pin "1") (pinfunction "1_1") (pintype "passive"))
      (node (ref "U2") (pin "7") (pinfunction "XI_7") (pintype "passive"))
      (node (ref "X2") (pin "2") (pinfunction "2_2") (pintype "passive"))
    )
    (net (code "51") (name "Net-(U2-XO)") (class "Default")
      (node (ref "C9") (pin "1") (pinfunction "1_1") (pintype "passive"))
      (node (ref "U2") (pin "8") (pinfunction "XO_8") (pintype "passive"))
      (node (ref "X2") (pin "1") (pinfunction "1_1") (pintype "passive"))
    )
    (net (code "52") (name "Net-(U6-CE)") (class "Default")
      (node (ref "R10") (pin "1") (pinfunction "1_1") (pintype "passive"))
      (node (ref "U6") (pin "8") (pinfunction "CE_8") (pintype "passive"))
    )
    (net (code "53") (name "Net-(U6-PROG)") (class "Default")
      (node (ref "R9") (pin "2") (pinfunction "2_2") (pintype "passive"))
      (node (ref "U6") (pin "2") (pinfunction "PROG_2") (pintype "passive"))
    )
    (net (code "54") (name "VCC") (class "Default")
      (node (ref "C1") (pin "2") (pinfunction "2_2") (pintype "passive"))
      (node (ref "C10") (pin "2") (pinfunction "2_2") (pintype "passive"))
      (node (ref "C2") (pin "2") (pinfunction "2_2") (pintype "passive"))
      (node (ref "C3") (pin "2") (pinfunction "2_2") (pintype "passive"))
      (node (ref "H1") (pin "2") (pinfunction "2_2") (pintype "passive"))
      (node (ref "R3") (pin "1") (pinfunction "1_1") (pintype "passive"))
      (node (ref "R4") (pin "1") (pinfunction "1_1") (pintype "passive"))
      (node (ref "R5") (pin "1") (pinfunction "1_1") (pintype "passive"))
      (node (ref "R6") (pin "1") (pinfunction "1_1") (pintype "passive"))
      (node (ref "U1") (pin "18") (pinfunction "AVCC_18") (pintype "passive"))
      (node (ref "U1") (pin "4") (pinfunction "VCC_4") (pintype "passive"))
      (node (ref "U1") (pin "6") (pinfunction "VCC_6") (pintype "passive"))
      (node (ref "U2") (pin "16") (pinfunction "VCC_16") (pintype "passive"))
    )
    (net (code "55") (name "VCC1") (class "Default")
      (node (ref "C17") (pin "1") (pinfunction "1_1") (pintype "passive"))
      (node (ref "C18") (pin "1") (pinfunction "1_1") (pintype "passive"))
      (node (ref "R10") (pin "2") (pinfunction "2_2") (pintype "passive"))
      (node (ref "R11") (pin "2") (pinfunction "2_2") (pintype "passive"))
      (node (ref "R12") (pin "2") (pinfunction "2_2") (pintype "passive"))
      (node (ref "R13") (pin "2") (pinfunction "2_2") (pintype "passive"))
      (node (ref "R7") (pin "1") (pinfunction "1_1") (pintype "passive"))
      (node (ref "U6") (pin "4") (pinfunction "VCC_4") (pintype "passive"))
    )
    (net (code "56") (name "unconnected-(SW2-Pad3)") (class "Default")
      (node (ref "SW2") (pin "3") (pinfunction "3_3") (pintype "passive"))
    )
    (net (code "57") (name "unconnected-(SW3-Pad3)") (class "Default")
      (node (ref "SW3") (pin "3") (pinfunction "3_3") (pintype "passive"))
    )
    (net (code "58") (name "unconnected-(SW3-Pad4)") (class "Default")
      (node (ref "SW3") (pin "4") (pinfunction "4_4") (pintype "passive"))
    )
    (net (code "59") (name "unconnected-(SW3-Pad5)") (class "Default")
      (node (ref "SW3") (pin "5") (pinfunction "5_5") (pintype "passive"))
    )
    (net (code "60") (name "unconnected-(SW3-Pad6)") (class "Default")
      (node (ref "SW3") (pin "6") (pinfunction "6_6") (pintype "passive"))
    )
    (net (code "61") (name "unconnected-(U2-CTS#-Pad9)") (class "Default")
      (node (ref "U2") (pin "9") (pinfunction "CTS#_9") (pintype "passive"))
    )
    (net (code "62") (name "unconnected-(U2-DCD#-Pad12)") (class "Default")
      (node (ref "U2") (pin "12") (pinfunction "DCD#_12") (pintype "passive"))
    )
    (net (code "63") (name "unconnected-(U2-DSR#-Pad10)") (class "Default")
      (node (ref "U2") (pin "10") (pinfunction "DSR#_10") (pintype "passive"))
    )
    (net (code "64") (name "unconnected-(U2-R232-Pad15)") (class "Default")
      (node (ref "U2") (pin "15") (pinfunction "R232_15") (pintype "passive"))
    )
    (net (code "65") (name "unconnected-(U2-RI#-Pad11)") (class "Default")
      (node (ref "U2") (pin "11") (pinfunction "RI#_11") (pintype "passive"))
    )
    (net (code "66") (name "unconnected-(U2-RTS#-Pad14)") (class "Default")
      (node (ref "U2") (pin "14") (pinfunction "RTS#_14") (pintype "passive"))
    )
    (net (code "67") (name "unconnected-(U4-NC-Pad3)") (class "Default")
      (node (ref "U4") (pin "3") (pinfunction "NC_3") (pintype "passive"))
    )
    (net (code "68") (name "unconnected-(U7-NC-Pad3)") (class "Default")
      (node (ref "U7") (pin "3") (pinfunction "NC_3") (pintype "passive"))
    )
    (net (code "69") (name "unconnected-(USB1-CC1-PadA5)") (class "Default")
      (node (ref "USB1") (pin "A5") (pinfunction "CC1_A5") (pintype "passive"))
    )
    (net (code "70") (name "unconnected-(USB1-CC2-PadB5)") (class "Default")
      (node (ref "USB1") (pin "B5") (pinfunction "CC2_B5") (pintype "passive"))
    )
    (net (code "71") (name "unconnected-(USB1-SBU1-PadA8)") (class "Default")
      (node (ref "USB1") (pin "A8") (pinfunction "SBU1_A8") (pintype "passive"))
    )
    (net (code "72") (name "unconnected-(USB1-SBU2-PadB8)") (class "Default")
      (node (ref "USB1") (pin "B8") (pinfunction "SBU2_B8") (pintype "passive"))
    )
  )
)
